# Sheet1.net
KiCad netlist of a schematic drawn in Altium Designer
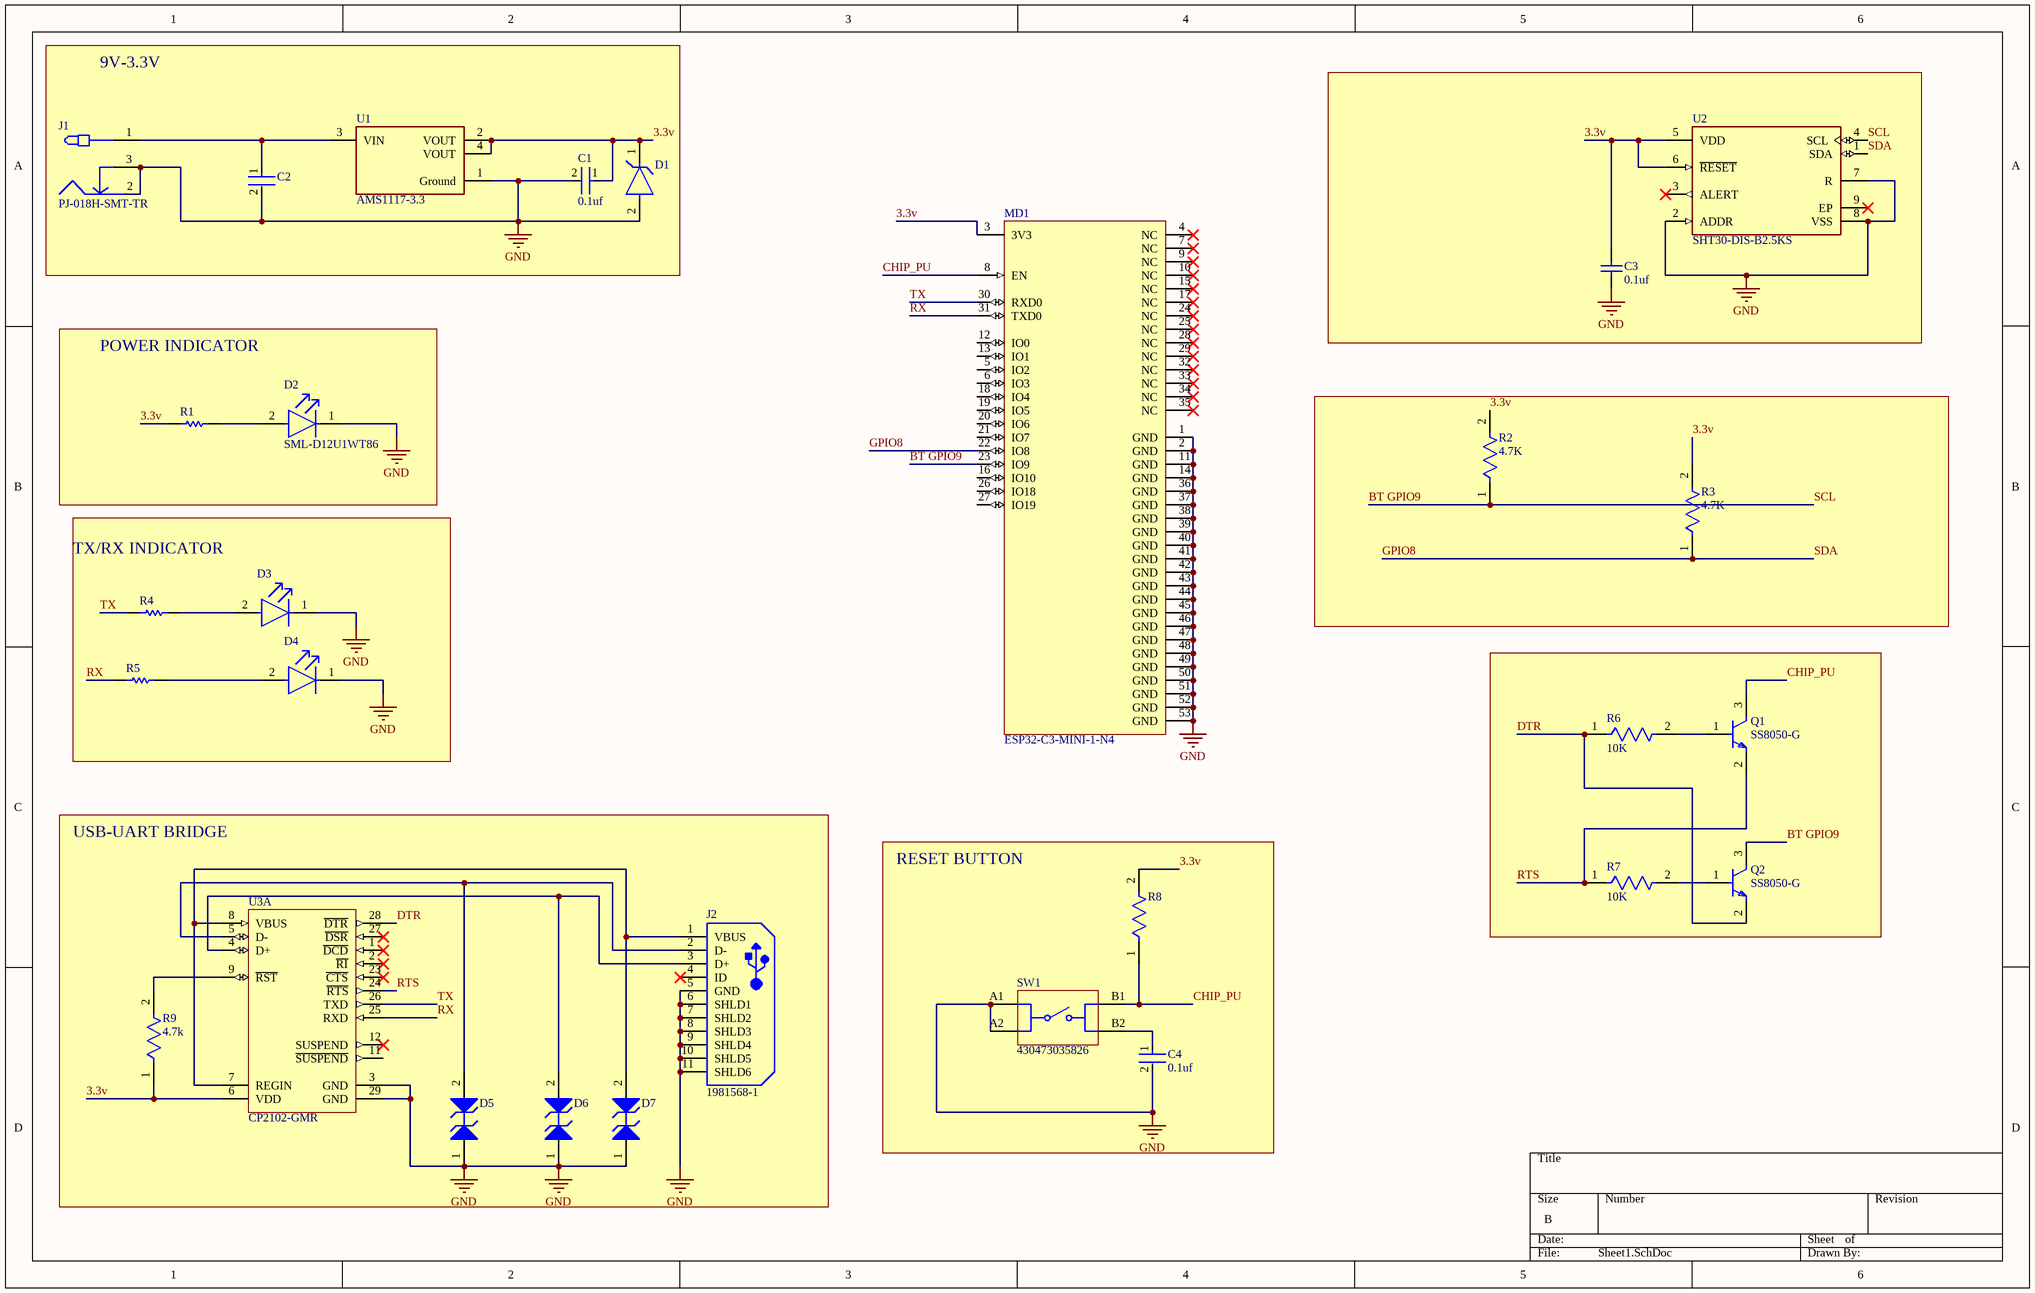
[diagram p0: Sheet1.SchDoc]

(export (version "E")
  (design (tool "Eeschema 10.0.6"))
  (components
    (comp (ref "C1")
      (value "0.1uf")
      (footprint "FP-0402B104K160CT-IPC_C")
      (description "CAP CER 0.1UF 16V X7R 0402")
      (fields (field (name "TOLERANCE") "10%"))
      (libsource (lib "Altium Content Vault") (part "b4654b650e69147ec39a6b967a45e02"))
    )
    (comp (ref "C2")
      (value "0402B104K160CT")
      (footprint "FP-0402B104K160CT-IPC_C")
      (description "CAP CER 0.1UF 16V X7R 0402")
      (fields (field (name "TOLERANCE") "10%"))
      (libsource (lib "Altium Content Vault") (part "b4654b650e69147ec39a6b967a45e02"))
    )
    (comp (ref "C3")
      (value "0.1uf")
      (footprint "CAPC1608X87X35ML15T15")
      (fields (field (name "PART NUMBER") "C0603T104K3RCLTU") (field (name "MANUFACTURER") "Kemet"))
      (libsource (lib "Altium Content Vault") (part "CAP"))
    )
    (comp (ref "C4")
      (value "0.1uf")
      (footprint "FP-0402B104K160CT-IPC_C")
      (description "CAP CER 0.1UF 16V X7R 0402")
      (fields (field (name "TOLERANCE") "10%"))
      (libsource (lib "Altium Content Vault") (part "b4654b650e69147ec39a6b967a45e02"))
    )
    (comp (ref "D1")
      (value "JANTX1N746AUR-1")
      (footprint "FP-DO-213AA-MFG")
      (description "JANTX1N746AUR-1 JANTX Series 3.3 V ±5 % 500 mW Through Hole Zener Diode - DO-213AA")
      (libsource (lib "Altium Content Vault") (part "f813f71cba58e380607f5dd3caf9714"))
    )
    (comp (ref "D2")
      (value "SML-D12U1WT86")
      (footprint "FP-SML-D12-MFG")
      (description "LED RED DIFFUSED 1608 SMD")
      (fields
        (field (name "MANUFACTURER") "Rohm")
        (field (name "OCTOPART") "https://octopart.com/sml-d12u1wt86-rohm-70850259")
      )
      (libsource (lib "Altium Content Vault") (part "8706943c75ba83719d021d2fdc84c58"))
    )
    (comp (ref "D3")
      (value "SML-D12U1WT86")
      (footprint "FP-SML-D12-MFG")
      (description "LED RED DIFFUSED 1608 SMD")
      (fields
        (field (name "MANUFACTURER") "Rohm")
        (field (name "OCTOPART") "https://octopart.com/sml-d12u1wt86-rohm-70850259")
      )
      (libsource (lib "Altium Content Vault") (part "8706943c75ba83719d021d2fdc84c58"))
    )
    (comp (ref "D4")
      (value "SML-D12U1WT86")
      (footprint "FP-SML-D12-MFG")
      (description "LED RED DIFFUSED 1608 SMD")
      (fields
        (field (name "MANUFACTURER") "Rohm")
        (field (name "OCTOPART") "https://octopart.com/sml-d12u1wt86-rohm-70850259")
      )
      (libsource (lib "Altium Content Vault") (part "8706943c75ba83719d021d2fdc84c58"))
    )
    (comp (ref "D5")
      (value "ESD9B5.0ST5G")
      (footprint "ONSC-SOD-923-2-514AB-01_V")
      (fields (field (name "MANUFACTURER") "On Semiconductor"))
      (libsource (lib "Altium Content Vault") (part "ONSC-A1A2-2"))
    )
    (comp (ref "D6")
      (value "ESD9B5.0ST5G")
      (footprint "ONSC-SOD-923-2-514AB-01_V")
      (fields (field (name "MANUFACTURER") "On Semiconductor"))
      (libsource (lib "Altium Content Vault") (part "ONSC-A1A2-2"))
    )
    (comp (ref "D7")
      (value "ESD9B5.0ST5G")
      (footprint "ONSC-SOD-923-2-514AB-01_V")
      (fields (field (name "MANUFACTURER") "On Semiconductor"))
      (libsource (lib "Altium Content Vault") (part "ONSC-A1A2-2"))
    )
    (comp (ref "J1")
      (value "PJ-018H-SMT-TR")
      (footprint "FP-PJ-018H-SMT-TR-MFG")
      (description "CONN PWR JACK 1.7X4MM SOLDER")
      (fields
        (field (name "OCTOPART") "https://octopart.com/pj-018h-smt-tr-cui-25947163")
        (field (name "MANUFACTURER") "CUI")
      )
      (libsource (lib "Altium Content Vault") (part "69f6362642411a5d0af2144c195d2b5"))
    )
    (comp (ref "J2")
      (value "1981568-1")
      (footprint "TECO-1981568-5_V")
      (description "Micro USB Receptacle Standard Type B Assy, 5-Pin SMD, RoHS, Tape and Reel")
      (fields (field (name "MANUFACTURER") "TE Connectivity"))
      (libsource (lib "Altium Content Vault") (part "USB-5-6SHLD"))
    )
    (comp (ref "MD1")
      (value "ESP32-C3-MINI-1-N4")
      (footprint "FP-ESP32-C3-MINI-1-N4-MFG")
      (description "Multiprotocol Modules SMD module, ESP32-C3FN4, PCB antenna, -40 C +85 C")
      (libsource (lib "Altium Content Vault") (part "ESP32-C3-MINI-1-N4"))
    )
    (comp (ref "Q1")
      (value "SS8050-G")
      (footprint "FP-SS8050-G-MFG")
      (description "NPN TRANSISTOR 1.5A 40V SOT-23 R")
      (libsource (lib "Altium Content Vault") (part "2a1388f82443b098dcd57d24ac7632d"))
    )
    (comp (ref "Q2")
      (value "SS8050-G")
      (footprint "FP-SS8050-G-MFG")
      (description "NPN TRANSISTOR 1.5A 40V SOT-23 R")
      (libsource (lib "Altium Content Vault") (part "2a1388f82443b098dcd57d24ac7632d"))
    )
    (comp (ref "R1")
      (value "RL0510S-R15-F")
      (footprint "RESC1005X45X15LL05T10")
      (fields (field (name "MANUFACTURER") "Susumu"))
      (libsource (lib "Altium Content Vault") (part "RES"))
    )
    (comp (ref "R2")
      (value "4.7K")
      (footprint "FP-TFCR0402-IPC_A")
      (description "RES Thin Film,  4.7kΩ, 0.5%, 0.063W, 25ppm/°C, 0402")
      (libsource (lib "Altium Content Vault") (part "1029c3af85768c4190bb7ad29bc67b5"))
    )
    (comp (ref "R3")
      (value "4.7K")
      (footprint "FP-TFCR0402-IPC_A")
      (description "RES Thin Film,  4.7kΩ, 0.5%, 0.063W, 25ppm/°C, 0402")
      (libsource (lib "Altium Content Vault") (part "1029c3af85768c4190bb7ad29bc67b5"))
    )
    (comp (ref "R4")
      (value "~")
      (footprint "RESC1005X45X15LL05T10")
      (fields (field (name "PART NUMBER") "RL0510S-R15-F") (field (name "MANUFACTURER") "Susumu"))
      (libsource (lib "Altium Content Vault") (part "RES"))
    )
    (comp (ref "R5")
      (value "RL0510S-R15-F")
      (footprint "RESC1005X45X15LL05T10")
      (fields (field (name "MANUFACTURER") "Susumu"))
      (libsource (lib "Altium Content Vault") (part "RES"))
    )
    (comp (ref "R6")
      (value "10K")
      (footprint "FP-CRCW0402-C-e3-IPC_C")
      (description "RES 10K OHM 1% 1/16W 0402")
      (fields (field (name "TOLERANCE") "1%"))
      (libsource (lib "Altium Content Vault") (part "1029c3af85768c4190bb7ad29bc67b5"))
    )
    (comp (ref "R7")
      (value "10K")
      (footprint "FP-CRCW0402-C-e3-IPC_C")
      (description "RES 10K OHM 1% 1/16W 0402")
      (fields (field (name "TOLERANCE") "1%"))
      (libsource (lib "Altium Content Vault") (part "1029c3af85768c4190bb7ad29bc67b5"))
    )
    (comp (ref "R8")
      (value "CRGCQ0402J10K")
      (footprint "FP-CRGCQ0402-IPC_C")
      (description "CRGCQ 0402 10K 5%")
      (fields
        (field (name "TOLERANCE") "0.05")
        (field (name "OCTOPART") "https://octopart.com/crgcq0402j10k-te+connectivity-91017993")
      )
      (libsource (lib "Altium Content Vault") (part "1029c3af85768c4190bb7ad29bc67b5"))
    )
    (comp (ref "R9")
      (value "4.7k")
      (footprint "FP-RC0402-0_4-MFG")
      (fields (field (name "TOLERANCE") "5%"))
      (libsource (lib "Altium Content Vault") (part "RC0402JR-074K7L"))
    )
    (comp (ref "SW1")
      (value "430473035826")
      (footprint "430473035826")
      (description "Switch Tactile Spst-no 0.05A 12V")
      (libsource (lib "Altium Content Vault") (part "SPST-NO_4P"))
    )
    (comp (ref "U1")
      (value "AMS1117-3.3")
      (footprint "FP-AMS1117-IPC_C")
      (description "LDO Voltage Regulators 1A, 3.3V")
      (fields
        (field (name "OCTOPART") "https://octopart.com/ams1117-3.3-advanced+monolithic+systems-25899300")
        (field (name "MANUFACTURER") "Advanced Monolithic Systems")
      )
      (libsource (lib "Altium Content Vault") (part "8bdbb5f8e77002000e30dd2845d0354"))
    )
    (comp (ref "U2")
      (value "SHT30-DIS-B2.5KS")
      (footprint "FP-SHT30-DIS-B2_5KS-MFG")
      (description "SENSOR HUMID/TEMP 5V I2C 3% SMD")
      (libsource (lib "Altium Content Vault") (part "3a40f6fddac460f1c5fb2adec20f0f2"))
    )
    (comp (ref "U3")
      (value "CP2102-GMR")
      (footprint "SLAB-QFN-28-3125x3125TP_M")
      (description "Single-Chip USB to URAT Bridge, 3.3 V, -40 to 85 degC, 28-Pin QFN, RoHS, Tape and Reel")
      (fields (field (name "MANUFACTURER") "Silicon Labs"))
      (libsource (lib "Altium Content Vault") (part "SLAB-CP210X-QFN-28-29"))
    )
  )
  (nets
    (net (code "1") (name "/3.3v") (class "Default")
      (node (ref "C1") (pin "1") (pinfunction "1_1") (pintype "passive"))
      (node (ref "C3") (pin "2") (pinfunction "2_2") (pintype "passive"))
      (node (ref "D1") (pin "1") (pinfunction "C_1") (pintype "passive"))
      (node (ref "MD1") (pin "3") (pinfunction "3V3_3") (pintype "power_in"))
      (node (ref "R1") (pin "1") (pinfunction "1_1") (pintype "passive"))
      (node (ref "R2") (pin "2") (pinfunction "2_2") (pintype "passive"))
      (node (ref "R3") (pin "2") (pinfunction "2_2") (pintype "passive"))
      (node (ref "R8") (pin "2") (pinfunction "2_2") (pintype "passive"))
      (node (ref "R9") (pin "1") (pinfunction "1_1") (pintype "passive"))
      (node (ref "U1") (pin "2") (pinfunction "VOUT_2") (pintype "passive"))
      (node (ref "U1") (pin "4") (pinfunction "VOUT_4") (pintype "passive"))
      (node (ref "U2") (pin "5") (pinfunction "VDD_5") (pintype "power_in"))
      (node (ref "U2") (pin "6") (pinfunction "~{RESET}_6") (pintype "input"))
      (node (ref "U3") (pin "6") (pinfunction "VDD_6") (pintype "power_in"))
    )
    (net (code "2") (name "/BT GPIO9") (class "Default")
      (node (ref "MD1") (pin "23") (pinfunction "IO9_23") (pintype "bidirectional"))
      (node (ref "Q2") (pin "3") (pinfunction "C_3") (pintype "passive"))
      (node (ref "R2") (pin "1") (pinfunction "1_1") (pintype "passive"))
      (node (ref "U2") (pin "4") (pinfunction "SCL_4") (pintype "bidirectional"))
    )
    (net (code "3") (name "/CHIP_PU") (class "Default")
      (node (ref "MD1") (pin "8") (pinfunction "EN_8") (pintype "input"))
      (node (ref "Q1") (pin "3") (pinfunction "C_3") (pintype "passive"))
      (node (ref "R8") (pin "1") (pinfunction "1_1") (pintype "passive"))
      (node (ref "SW1") (pin "B1") (pinfunction "B1_B1") (pintype "passive"))
    )
    (net (code "4") (name "/DTR") (class "Default")
      (node (ref "Q2") (pin "2") (pinfunction "E_2") (pintype "passive"))
      (node (ref "R6") (pin "1") (pinfunction "1_1") (pintype "passive"))
      (node (ref "U3") (pin "28") (pinfunction "~{DTR}_28") (pintype "output"))
    )
    (net (code "5") (name "/GPIO8") (class "Default")
      (node (ref "MD1") (pin "22") (pinfunction "IO8_22") (pintype "bidirectional"))
      (node (ref "R3") (pin "1") (pinfunction "1_1") (pintype "passive"))
      (node (ref "U2") (pin "1") (pinfunction "SDA_1") (pintype "bidirectional"))
    )
    (net (code "6") (name "/RTS") (class "Default")
      (node (ref "Q1") (pin "2") (pinfunction "E_2") (pintype "passive"))
      (node (ref "R7") (pin "1") (pinfunction "1_1") (pintype "passive"))
      (node (ref "U3") (pin "24") (pinfunction "~{RTS}_24") (pintype "output"))
    )
    (net (code "7") (name "/RX") (class "Default")
      (node (ref "MD1") (pin "31") (pinfunction "TXD0_31") (pintype "bidirectional"))
      (node (ref "R5") (pin "1") (pinfunction "1_1") (pintype "passive"))
      (node (ref "U3") (pin "25") (pinfunction "RXD_25") (pintype "input"))
    )
    (net (code "8") (name "/TX") (class "Default")
      (node (ref "MD1") (pin "30") (pinfunction "RXD0_30") (pintype "bidirectional"))
      (node (ref "R4") (pin "1") (pinfunction "1_1") (pintype "passive"))
      (node (ref "U3") (pin "26") (pinfunction "TXD_26") (pintype "output"))
    )
    (net (code "9") (name "GND") (class "Default")
      (node (ref "C1") (pin "2") (pinfunction "2_2") (pintype "passive"))
      (node (ref "C2") (pin "2") (pinfunction "2_2") (pintype "passive"))
      (node (ref "C3") (pin "1") (pinfunction "1_1") (pintype "passive"))
      (node (ref "C4") (pin "2") (pinfunction "2_2") (pintype "passive"))
      (node (ref "D1") (pin "2") (pinfunction "A_2") (pintype "passive"))
      (node (ref "D2") (pin "1") (pinfunction "C_1") (pintype "passive"))
      (node (ref "D3") (pin "1") (pinfunction "C_1") (pintype "passive"))
      (node (ref "D4") (pin "1") (pinfunction "C_1") (pintype "passive"))
      (node (ref "D5") (pin "1") (pinfunction "A1_1") (pintype "passive"))
      (node (ref "D6") (pin "1") (pinfunction "A1_1") (pintype "passive"))
      (node (ref "D7") (pin "1") (pinfunction "A1_1") (pintype "passive"))
      (node (ref "J1") (pin "2") (pinfunction "2_2") (pintype "passive"))
      (node (ref "J1") (pin "3") (pinfunction "3_3") (pintype "passive"))
      (node (ref "J2") (pin "10") (pinfunction "SHLD5_10") (pintype "passive"))
      (node (ref "J2") (pin "11") (pinfunction "SHLD6_11") (pintype "passive"))
      (node (ref "J2") (pin "5") (pinfunction "GND_5") (pintype "passive"))
      (node (ref "J2") (pin "6") (pinfunction "SHLD1_6") (pintype "passive"))
      (node (ref "J2") (pin "7") (pinfunction "SHLD2_7") (pintype "passive"))
      (node (ref "J2") (pin "8") (pinfunction "SHLD3_8") (pintype "passive"))
      (node (ref "J2") (pin "9") (pinfunction "SHLD4_9") (pintype "passive"))
      (node (ref "MD1") (pin "1") (pinfunction "GND_1") (pintype "power_in"))
      (node (ref "MD1") (pin "11") (pinfunction "GND_11") (pintype "power_in"))
      (node (ref "MD1") (pin "14") (pinfunction "GND_14") (pintype "power_in"))
      (node (ref "MD1") (pin "2") (pinfunction "GND_2") (pintype "power_in"))
      (node (ref "MD1") (pin "36") (pinfunction "GND_36") (pintype "power_in"))
      (node (ref "MD1") (pin "37") (pinfunction "GND_37") (pintype "power_in"))
      (node (ref "MD1") (pin "38") (pinfunction "GND_38") (pintype "power_in"))
      (node (ref "MD1") (pin "39") (pinfunction "GND_39") (pintype "power_in"))
      (node (ref "MD1") (pin "40") (pinfunction "GND_40") (pintype "power_in"))
      (node (ref "MD1") (pin "41") (pinfunction "GND_41") (pintype "power_in"))
      (node (ref "MD1") (pin "42") (pinfunction "GND_42") (pintype "power_in"))
      (node (ref "MD1") (pin "43") (pinfunction "GND_43") (pintype "power_in"))
      (node (ref "MD1") (pin "44") (pinfunction "GND_44") (pintype "power_in"))
      (node (ref "MD1") (pin "45") (pinfunction "GND_45") (pintype "power_in"))
      (node (ref "MD1") (pin "46") (pinfunction "GND_46") (pintype "power_in"))
      (node (ref "MD1") (pin "47") (pinfunction "GND_47") (pintype "power_in"))
      (node (ref "MD1") (pin "48") (pinfunction "GND_48") (pintype "power_in"))
      (node (ref "MD1") (pin "49") (pinfunction "GND_49") (pintype "power_in"))
      (node (ref "MD1") (pin "50") (pinfunction "GND_50") (pintype "power_in"))
      (node (ref "MD1") (pin "51") (pinfunction "GND_51") (pintype "power_in"))
      (node (ref "MD1") (pin "52") (pinfunction "GND_52") (pintype "power_in"))
      (node (ref "MD1") (pin "53") (pinfunction "GND_53") (pintype "power_in"))
      (node (ref "SW1") (pin "A1") (pinfunction "A1_A1") (pintype "passive"))
      (node (ref "SW1") (pin "A2") (pinfunction "A2_A2") (pintype "passive"))
      (node (ref "U1") (pin "1") (pinfunction "Ground_1") (pintype "power_in"))
      (node (ref "U2") (pin "2") (pinfunction "ADDR_2") (pintype "input"))
      (node (ref "U2") (pin "7") (pinfunction "R_7") (pintype "passive"))
      (node (ref "U2") (pin "8") (pinfunction "VSS_8") (pintype "power_in"))
      (node (ref "U3") (pin "29") (pinfunction "GND_29") (pintype "power_in"))
      (node (ref "U3") (pin "3") (pinfunction "GND_3") (pintype "power_in"))
    )
    (net (code "10") (name "Net-(C4-Pad1)") (class "Default")
      (node (ref "C4") (pin "1") (pinfunction "1_1") (pintype "passive"))
      (node (ref "SW1") (pin "B2") (pinfunction "B2_B2") (pintype "passive"))
    )
    (net (code "11") (name "Net-(D2-A)") (class "Default")
      (node (ref "D2") (pin "2") (pinfunction "A_2") (pintype "passive"))
      (node (ref "R1") (pin "2") (pinfunction "2_2") (pintype "passive"))
    )
    (net (code "12") (name "Net-(D3-A)") (class "Default")
      (node (ref "D3") (pin "2") (pinfunction "A_2") (pintype "passive"))
      (node (ref "R4") (pin "2") (pinfunction "2_2") (pintype "passive"))
    )
    (net (code "13") (name "Net-(D4-A)") (class "Default")
      (node (ref "D4") (pin "2") (pinfunction "A_2") (pintype "passive"))
      (node (ref "R5") (pin "2") (pinfunction "2_2") (pintype "passive"))
    )
    (net (code "14") (name "Net-(D5-A2)") (class "Default")
      (node (ref "D5") (pin "2") (pinfunction "A2_2") (pintype "passive"))
      (node (ref "J2") (pin "2") (pinfunction "D-_2") (pintype "passive"))
      (node (ref "U3") (pin "5") (pinfunction "D-_5") (pintype "bidirectional"))
    )
    (net (code "15") (name "Net-(D6-A2)") (class "Default")
      (node (ref "D6") (pin "2") (pinfunction "A2_2") (pintype "passive"))
      (node (ref "J2") (pin "3") (pinfunction "D+_3") (pintype "passive"))
      (node (ref "U3") (pin "4") (pinfunction "D+_4") (pintype "bidirectional"))
    )
    (net (code "16") (name "Net-(D7-A2)") (class "Default")
      (node (ref "D7") (pin "2") (pinfunction "A2_2") (pintype "passive"))
      (node (ref "J2") (pin "1") (pinfunction "VBUS_1") (pintype "passive"))
      (node (ref "U3") (pin "7") (pinfunction "REGIN_7") (pintype "power_in"))
      (node (ref "U3") (pin "8") (pinfunction "VBUS_8") (pintype "input"))
    )
    (net (code "17") (name "Net-(Q1-B)") (class "Default")
      (node (ref "Q1") (pin "1") (pinfunction "B_1") (pintype "passive"))
      (node (ref "R6") (pin "2") (pinfunction "2_2") (pintype "passive"))
    )
    (net (code "18") (name "Net-(Q2-B)") (class "Default")
      (node (ref "Q2") (pin "1") (pinfunction "B_1") (pintype "passive"))
      (node (ref "R7") (pin "2") (pinfunction "2_2") (pintype "passive"))
    )
    (net (code "19") (name "Net-(U1-VIN)") (class "Default")
      (node (ref "C2") (pin "1") (pinfunction "1_1") (pintype "passive"))
      (node (ref "J1") (pin "1") (pinfunction "1_1") (pintype "passive"))
      (node (ref "U1") (pin "3") (pinfunction "VIN_3") (pintype "power_in"))
    )
    (net (code "20") (name "Net-(U3A-~{RST})") (class "Default")
      (node (ref "R9") (pin "2") (pinfunction "2_2") (pintype "passive"))
      (node (ref "U3") (pin "9") (pinfunction "~{RST}_9") (pintype "bidirectional"))
    )
    (net (code "21") (name "unconnected-(J2-ID-Pad4)") (class "Default")
      (node (ref "J2") (pin "4") (pinfunction "ID_4") (pintype "passive+no_connect"))
    )
    (net (code "22") (name "unconnected-(MD1-IO0-Pad12)") (class "Default")
      (node (ref "MD1") (pin "12") (pinfunction "IO0_12") (pintype "bidirectional"))
    )
    (net (code "23") (name "unconnected-(MD1-IO1-Pad13)") (class "Default")
      (node (ref "MD1") (pin "13") (pinfunction "IO1_13") (pintype "bidirectional"))
    )
    (net (code "24") (name "unconnected-(MD1-IO2-Pad5)") (class "Default")
      (node (ref "MD1") (pin "5") (pinfunction "IO2_5") (pintype "bidirectional"))
    )
    (net (code "25") (name "unconnected-(MD1-IO3-Pad6)") (class "Default")
      (node (ref "MD1") (pin "6") (pinfunction "IO3_6") (pintype "bidirectional"))
    )
    (net (code "26") (name "unconnected-(MD1-IO4-Pad18)") (class "Default")
      (node (ref "MD1") (pin "18") (pinfunction "IO4_18") (pintype "bidirectional"))
    )
    (net (code "27") (name "unconnected-(MD1-IO5-Pad19)") (class "Default")
      (node (ref "MD1") (pin "19") (pinfunction "IO5_19") (pintype "bidirectional"))
    )
    (net (code "28") (name "unconnected-(MD1-IO6-Pad20)") (class "Default")
      (node (ref "MD1") (pin "20") (pinfunction "IO6_20") (pintype "bidirectional"))
    )
    (net (code "29") (name "unconnected-(MD1-IO7-Pad21)") (class "Default")
      (node (ref "MD1") (pin "21") (pinfunction "IO7_21") (pintype "bidirectional"))
    )
    (net (code "30") (name "unconnected-(MD1-IO10-Pad16)") (class "Default")
      (node (ref "MD1") (pin "16") (pinfunction "IO10_16") (pintype "bidirectional"))
    )
    (net (code "31") (name "unconnected-(MD1-IO18-Pad26)") (class "Default")
      (node (ref "MD1") (pin "26") (pinfunction "IO18_26") (pintype "bidirectional"))
    )
    (net (code "32") (name "unconnected-(MD1-IO19-Pad27)") (class "Default")
      (node (ref "MD1") (pin "27") (pinfunction "IO19_27") (pintype "bidirectional"))
    )
    (net (code "33") (name "unconnected-(MD1-NC-Pad4)") (class "Default")
      (node (ref "MD1") (pin "4") (pinfunction "NC_4") (pintype "passive+no_connect"))
    )
    (net (code "34") (name "unconnected-(MD1-NC-Pad7)") (class "Default")
      (node (ref "MD1") (pin "7") (pinfunction "NC_7") (pintype "passive+no_connect"))
    )
    (net (code "35") (name "unconnected-(MD1-NC-Pad9)") (class "Default")
      (node (ref "MD1") (pin "9") (pinfunction "NC_9") (pintype "passive+no_connect"))
    )
    (net (code "36") (name "unconnected-(MD1-NC-Pad10)") (class "Default")
      (node (ref "MD1") (pin "10") (pinfunction "NC_10") (pintype "passive+no_connect"))
    )
    (net (code "37") (name "unconnected-(MD1-NC-Pad15)") (class "Default")
      (node (ref "MD1") (pin "15") (pinfunction "NC_15") (pintype "passive+no_connect"))
    )
    (net (code "38") (name "unconnected-(MD1-NC-Pad17)") (class "Default")
      (node (ref "MD1") (pin "17") (pinfunction "NC_17") (pintype "passive+no_connect"))
    )
    (net (code "39") (name "unconnected-(MD1-NC-Pad24)") (class "Default")
      (node (ref "MD1") (pin "24") (pinfunction "NC_24") (pintype "passive+no_connect"))
    )
    (net (code "40") (name "unconnected-(MD1-NC-Pad25)") (class "Default")
      (node (ref "MD1") (pin "25") (pinfunction "NC_25") (pintype "passive+no_connect"))
    )
    (net (code "41") (name "unconnected-(MD1-NC-Pad28)") (class "Default")
      (node (ref "MD1") (pin "28") (pinfunction "NC_28") (pintype "passive+no_connect"))
    )
    (net (code "42") (name "unconnected-(MD1-NC-Pad29)") (class "Default")
      (node (ref "MD1") (pin "29") (pinfunction "NC_29") (pintype "passive+no_connect"))
    )
    (net (code "43") (name "unconnected-(MD1-NC-Pad32)") (class "Default")
      (node (ref "MD1") (pin "32") (pinfunction "NC_32") (pintype "passive+no_connect"))
    )
    (net (code "44") (name "unconnected-(MD1-NC-Pad33)") (class "Default")
      (node (ref "MD1") (pin "33") (pinfunction "NC_33") (pintype "passive+no_connect"))
    )
    (net (code "45") (name "unconnected-(MD1-NC-Pad34)") (class "Default")
      (node (ref "MD1") (pin "34") (pinfunction "NC_34") (pintype "passive+no_connect"))
    )
    (net (code "46") (name "unconnected-(MD1-NC-Pad35)") (class "Default")
      (node (ref "MD1") (pin "35") (pinfunction "NC_35") (pintype "passive+no_connect"))
    )
    (net (code "47") (name "unconnected-(U2-ALERT-Pad3)") (class "Default")
      (node (ref "U2") (pin "3") (pinfunction "ALERT_3") (pintype "output+no_connect"))
    )
    (net (code "48") (name "unconnected-(U2-EP-Pad9)") (class "Default")
      (node (ref "U2") (pin "9") (pinfunction "EP_9") (pintype "passive+no_connect"))
    )
    (net (code "49") (name "unconnected-(U3A-SUSPEND-Pad12)") (class "Default")
      (node (ref "U3") (pin "12") (pinfunction "SUSPEND_12") (pintype "output+no_connect"))
    )
    (net (code "50") (name "unconnected-(U3A-~{CTS}-Pad23)") (class "Default")
      (node (ref "U3") (pin "23") (pinfunction "~{CTS}_23") (pintype "input+no_connect"))
    )
    (net (code "51") (name "unconnected-(U3A-~{DCD}-Pad1)") (class "Default")
      (node (ref "U3") (pin "1") (pinfunction "~{DCD}_1") (pintype "input+no_connect"))
    )
    (net (code "52") (name "unconnected-(U3A-~{DSR}-Pad27)") (class "Default")
      (node (ref "U3") (pin "27") (pinfunction "~{DSR}_27") (pintype "input+no_connect"))
    )
    (net (code "53") (name "unconnected-(U3A-~{RI}-Pad2)") (class "Default")
      (node (ref "U3") (pin "2") (pinfunction "~{RI}_2") (pintype "input+no_connect"))
    )
    (net (code "54") (name "unconnected-(U3A-~{SUSPEND}-Pad11)") (class "Default")
      (node (ref "U3") (pin "11") (pinfunction "~{SUSPEND}_11") (pintype "output"))
    )
  )
)
